# Filters.net
KiCad netlist of a schematic drawn in Altium Designer
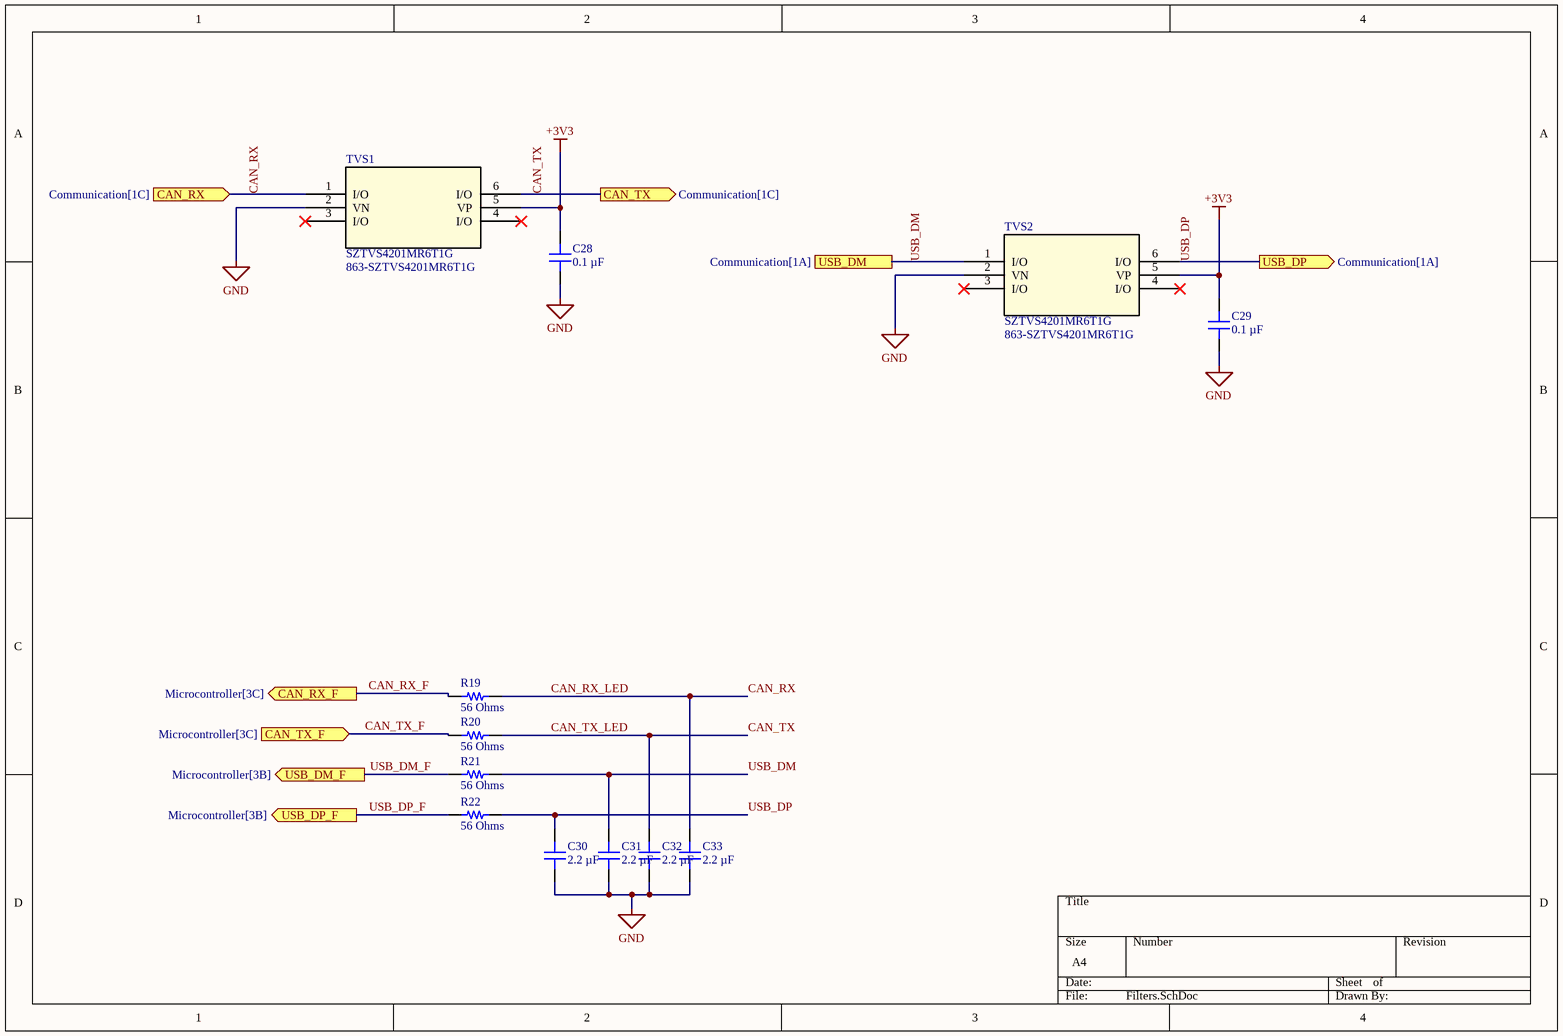
[diagram p0: Filters.SchDoc]

(export (version "E")
  (design (tool "Eeschema 10.0.6"))
  (components
    (comp (ref "C28")
      (value "0.1 µF")
      (footprint "CAP 0805_2012")
      (description "CAP CER 0.1UF 50V X7R 0805")
      (fields (field (name "PART NUMBER") "CC0805MRX7R9BB104") (field (name "MANUFACTURER") "Yageo"))
      (libsource (lib "Celestial Altium Library - altium_library (2)") (part "Capacitor"))
    )
    (comp (ref "C29")
      (value "0.1 µF")
      (footprint "CAP 0805_2012")
      (description "CAP CER 0.1UF 50V X7R 0805")
      (fields (field (name "PART NUMBER") "CC0805MRX7R9BB104") (field (name "MANUFACTURER") "Yageo"))
      (libsource (lib "Celestial Altium Library - altium_library (2)") (part "Capacitor"))
    )
    (comp (ref "C30")
      (value "2.2 µF")
      (footprint "CAP 0805_2012")
      (description "CAP CER 2.2UF 25V X7R 0805")
      (fields (field (name "PART NUMBER") "TMK212B7225MG-TR") (field (name "MANUFACTURER") "Taiyo Yuden"))
      (libsource (lib "Celestial Altium Library - altium_library (2)") (part "Capacitor"))
    )
    (comp (ref "C31")
      (value "2.2 µF")
      (footprint "CAP 0805_2012")
      (description "CAP CER 2.2UF 25V X7R 0805")
      (fields (field (name "PART NUMBER") "TMK212B7225MG-TR") (field (name "MANUFACTURER") "Taiyo Yuden"))
      (libsource (lib "Celestial Altium Library - altium_library (2)") (part "Capacitor"))
    )
    (comp (ref "C32")
      (value "2.2 µF")
      (footprint "CAP 0805_2012")
      (description "CAP CER 2.2UF 25V X7R 0805")
      (fields (field (name "PART NUMBER") "TMK212B7225MG-TR") (field (name "MANUFACTURER") "Taiyo Yuden"))
      (libsource (lib "Celestial Altium Library - altium_library (2)") (part "Capacitor"))
    )
    (comp (ref "C33")
      (value "2.2 µF")
      (footprint "CAP 0805_2012")
      (description "CAP CER 2.2UF 25V X7R 0805")
      (fields (field (name "PART NUMBER") "TMK212B7225MG-TR") (field (name "MANUFACTURER") "Taiyo Yuden"))
      (libsource (lib "Celestial Altium Library - altium_library (2)") (part "Capacitor"))
    )
    (comp (ref "R19")
      (value "56 Ohms")
      (footprint "RES 0805_2012")
      (description "RES SMD 56 OHM 0.1% 1/10W 0805")
      (fields
        (field (name "PART NUMBER") "CPF0805B56RE1")
        (field (name "MANUFACTURER") "TE Connectivity Passive Product")
      )
      (libsource (lib "Celestial Altium Library - altium_library (2)") (part "Resistor"))
    )
    (comp (ref "R20")
      (value "56 Ohms")
      (footprint "RES 0805_2012")
      (description "RES SMD 56 OHM 0.1% 1/10W 0805")
      (fields
        (field (name "PART NUMBER") "CPF0805B56RE1")
        (field (name "MANUFACTURER") "TE Connectivity Passive Product")
      )
      (libsource (lib "Celestial Altium Library - altium_library (2)") (part "Resistor"))
    )
    (comp (ref "R21")
      (value "56 Ohms")
      (footprint "RES 0805_2012")
      (description "RES SMD 56 OHM 0.1% 1/10W 0805")
      (fields
        (field (name "PART NUMBER") "CPF0805B56RE1")
        (field (name "MANUFACTURER") "TE Connectivity Passive Product")
      )
      (libsource (lib "Celestial Altium Library - altium_library (2)") (part "Resistor"))
    )
    (comp (ref "R22")
      (value "56 Ohms")
      (footprint "RES 0805_2012")
      (description "RES SMD 56 OHM 0.1% 1/10W 0805")
      (fields
        (field (name "PART NUMBER") "CPF0805B56RE1")
        (field (name "MANUFACTURER") "TE Connectivity Passive Product")
      )
      (libsource (lib "Celestial Altium Library - altium_library (2)") (part "Resistor"))
    )
    (comp (ref "TVS1")
      (value "SZTVS4201MR6T1G")
      (footprint "SOP95P275X110-6N")
      (fields
        (field (name "SUPPLIER PART NUMBER 1") "863-SZTVS4201MR6T1G")
        (field (name "COPYRIGHT") "Copyright (C) 2021 Ultra Librarian. All rights reserved.")
      )
      (libsource (lib "Schlib1") (part "SZTVS4201MR6T1G_1"))
    )
    (comp (ref "TVS2")
      (value "SZTVS4201MR6T1G")
      (footprint "SOP95P275X110-6N")
      (fields
        (field (name "SUPPLIER PART NUMBER 1") "863-SZTVS4201MR6T1G")
        (field (name "COPYRIGHT") "Copyright (C) 2021 Ultra Librarian. All rights reserved.")
      )
      (libsource (lib "Schlib1") (part "SZTVS4201MR6T1G_1"))
    )
  )
  (nets
    (net (code "1") (name "+3V3") (class "Default")
      (node (ref "C28") (pin "2") (pinfunction "2_2") (pintype "passive"))
      (node (ref "C29") (pin "2") (pinfunction "2_2") (pintype "passive"))
      (node (ref "TVS1") (pin "5") (pinfunction "VP_5") (pintype "passive"))
      (node (ref "TVS2") (pin "5") (pinfunction "VP_5") (pintype "passive"))
    )
    (net (code "2") (name "/CAN_RX") (class "Default")
      (node (ref "C33") (pin "2") (pinfunction "2_2") (pintype "passive"))
      (node (ref "R19") (pin "2") (pinfunction "2_2") (pintype "passive"))
      (node (ref "TVS1") (pin "1") (pinfunction "I/O_1") (pintype "passive"))
    )
    (net (code "3") (name "/CAN_RX_F") (class "Default")
      (node (ref "R19") (pin "1") (pinfunction "1_1") (pintype "passive"))
    )
    (net (code "4") (name "/CAN_TX") (class "Default")
      (node (ref "C32") (pin "2") (pinfunction "2_2") (pintype "passive"))
      (node (ref "R20") (pin "2") (pinfunction "2_2") (pintype "passive"))
      (node (ref "TVS1") (pin "6") (pinfunction "I/O_6") (pintype "passive"))
    )
    (net (code "5") (name "/CAN_TX_F") (class "Default")
      (node (ref "R20") (pin "1") (pinfunction "1_1") (pintype "passive"))
    )
    (net (code "6") (name "/USB_DM") (class "Default")
      (node (ref "C31") (pin "2") (pinfunction "2_2") (pintype "passive"))
      (node (ref "R21") (pin "2") (pinfunction "2_2") (pintype "passive"))
      (node (ref "TVS2") (pin "1") (pinfunction "I/O_1") (pintype "passive"))
    )
    (net (code "7") (name "/USB_DM_F") (class "Default")
      (node (ref "R21") (pin "1") (pinfunction "1_1") (pintype "passive"))
    )
    (net (code "8") (name "/USB_DP") (class "Default")
      (node (ref "C30") (pin "2") (pinfunction "2_2") (pintype "passive"))
      (node (ref "R22") (pin "2") (pinfunction "2_2") (pintype "passive"))
      (node (ref "TVS2") (pin "6") (pinfunction "I/O_6") (pintype "passive"))
    )
    (net (code "9") (name "/USB_DP_F") (class "Default")
      (node (ref "R22") (pin "1") (pinfunction "1_1") (pintype "passive"))
    )
    (net (code "10") (name "GND") (class "Default")
      (node (ref "C28") (pin "1") (pinfunction "1_1") (pintype "passive"))
      (node (ref "C29") (pin "1") (pinfunction "1_1") (pintype "passive"))
      (node (ref "C30") (pin "1") (pinfunction "1_1") (pintype "passive"))
      (node (ref "C31") (pin "1") (pinfunction "1_1") (pintype "passive"))
      (node (ref "C32") (pin "1") (pinfunction "1_1") (pintype "passive"))
      (node (ref "C33") (pin "1") (pinfunction "1_1") (pintype "passive"))
      (node (ref "TVS1") (pin "2") (pinfunction "VN_2") (pintype "passive"))
      (node (ref "TVS2") (pin "2") (pinfunction "VN_2") (pintype "passive"))
    )
    (net (code "11") (name "unconnected-(TVS1-I{slash}O-Pad3)") (class "Default")
      (node (ref "TVS1") (pin "3") (pinfunction "I/O_3") (pintype "passive+no_connect"))
    )
    (net (code "12") (name "unconnected-(TVS1-I{slash}O-Pad4)") (class "Default")
      (node (ref "TVS1") (pin "4") (pinfunction "I/O_4") (pintype "passive+no_connect"))
    )
    (net (code "13") (name "unconnected-(TVS2-I{slash}O-Pad3)") (class "Default")
      (node (ref "TVS2") (pin "3") (pinfunction "I/O_3") (pintype "passive+no_connect"))
    )
    (net (code "14") (name "unconnected-(TVS2-I{slash}O-Pad4)") (class "Default")
      (node (ref "TVS2") (pin "4") (pinfunction "I/O_4") (pintype "passive+no_connect"))
    )
  )
)
